# Boost_12V.net
KiCad netlist of a schematic drawn in Altium Designer
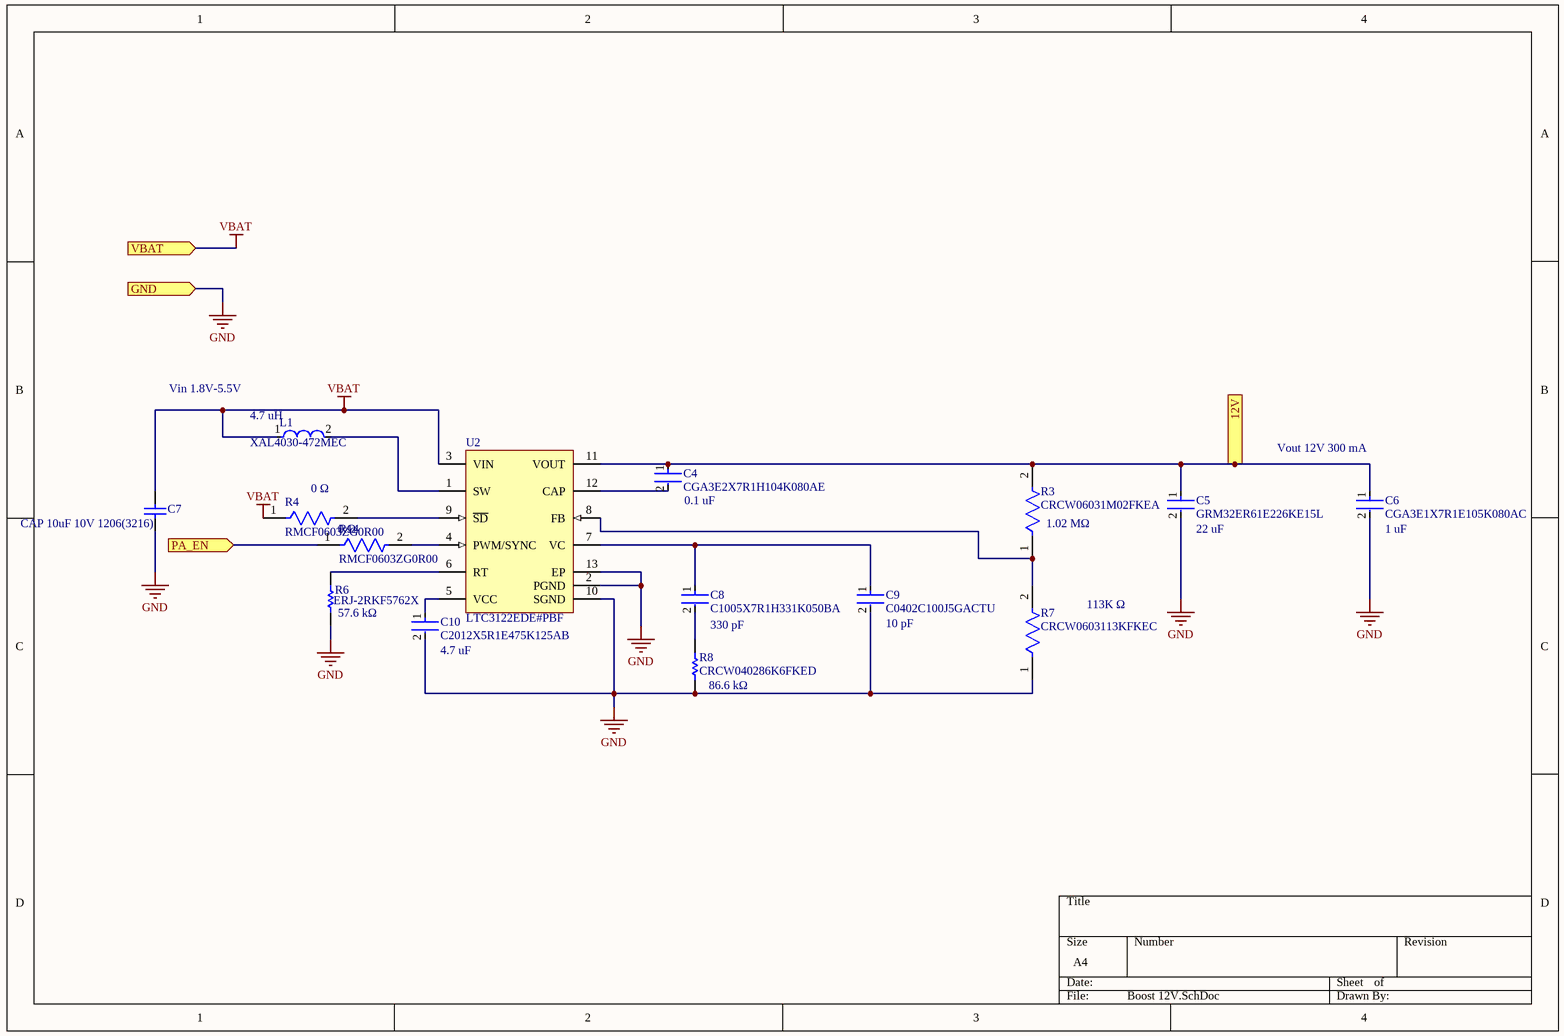
[diagram p0: Boost 12V.SchDoc]

(export (version "E")
  (design (tool "Eeschema 10.0.6"))
  (components
    (comp (ref "C4")
      (value "CGA3E2X7R1H104K080AE")
      (footprint "FP-CGA3E-0_3-0_1-IPC_A")
      (description "Cap Ceramic 100nF 50V X7R 10% Pad SMD 0603 +125°C Automotive T/R")
      (fields (field (name "TOLERANCE") "10%"))
      (libsource (lib "Altium Content Vault") (part "b4654b650e69147ec39a6b967a45e02"))
    )
    (comp (ref "C5")
      (value "GRM32ER61E226KE15L")
      (footprint "FP-GRM32-MFG")
      (description "CAP CER 22UF 25V X5R 1210")
      (fields
        (field (name "TOLERANCE") "10%")
        (field (name "MANUFACTURER") "Murata Electronics North America")
      )
      (libsource (lib "Altium Content Vault") (part "11868f565c42a9108669ba33697ecf6"))
    )
    (comp (ref "C6")
      (value "CGA3E1X7R1E105K080AC")
      (footprint "FP-CGA3E-0_3-0_1-IPC_A")
      (description "Cap Ceramic 1uF 25V X7R 10% Pad SMD 0603 +125°C Automotive T/R")
      (fields (field (name "VOLTAGE") "25V") (field (name "TOLERANCE") "10%"))
      (libsource (lib "Altium Content Vault") (part "b4654b650e69147ec39a6b967a45e02"))
    )
    (comp (ref "C7")
      (value "CAP 10uF 10V 1206(3216)")
      (footprint "CAPC1206(3216)190_L")
      (description "CAP 10uF 10V ±10% 1206 (3216 Metric) Thickness 1.9mm SMD")
      (fields (field (name "TOLERANCE") "Â±10%"))
      (libsource (lib "Altium Content Vault") (part "CAP"))
    )
    (comp (ref "C8")
      (value "C1005X7R1H331K050BA")
      (footprint "FP-C1005-050-0_05-IPC_B")
      (description "Multilayer Ceramic Capacitors 330pF ±10% 50V X7R SMD 0402")
      (fields (field (name "TOLERANCE") "10%"))
      (libsource (lib "Altium Content Vault") (part "b4654b650e69147ec39a6b967a45e02"))
    )
    (comp (ref "C9")
      (value "C0402C100J5GACTU")
      (footprint "FP-C0402-BB-MFG")
      (fields
        (field (name "MANUFACTURER") "Kemet")
        (field (name "OCTOPART") "https://octopart.com/c0402c100j5gactu-kemet-108448")
        (field (name "TOLERANCE") "0.05")
      )
      (libsource (lib "Altium Content Vault") (part "b4654b650e69147ec39a6b967a45e02"))
    )
    (comp (ref "C10")
      (value "C2012X5R1E475K125AB")
      (footprint "FP-C2012-125-0_2-MFG")
      (description "Multilayer Ceramic Capacitors 4.7μF ±10% 25V X5R SMD 0805")
      (fields (field (name "VOLTAGE") "25V") (field (name "TOLERANCE") "10%"))
      (libsource (lib "Altium Content Vault") (part "b4654b650e69147ec39a6b967a45e02"))
    )
    (comp (ref "L1")
      (value "XAL4030-472MEC")
      (footprint "FP-XAL4030-472MEC-MFG")
      (description "Power Inductor (SMD), 4.7 µH, 5.1 A, Shielded, 4.5 A, XAL40xx Series, 4mm x 4mm x 3.1mm")
      (fields (field (name "TOLERANCE") "20%"))
      (libsource (lib "Altium Content Vault") (part "725321dda6339637d4d059423bc1c3c"))
    )
    (comp (ref "R3")
      (value "CRCW06031M02FKEA")
      (footprint "FP-CRCW0603-e3-IPC_A")
      (description "RES Thick Film, 1.02MΩ, 1%, 0.1W, 100ppm/°C, 0603")
      (fields (field (name "TOLERANCE") "1%"))
      (libsource (lib "Altium Content Vault") (part "1029c3af85768c4190bb7ad29bc67b5"))
    )
    (comp (ref "R4")
      (value "RMCF0603ZG0R00")
      (footprint "FP-RMCF0603-IPC_B")
      (description "0Ω ±0 0.1W 0603 Thick Film Chip Resistor AEC-Q200 compliant")
      (libsource (lib "Altium Content Vault") (part "1029c3af85768c4190bb7ad29bc67b5"))
    )
    (comp (ref "R6")
      (value "ERJ-2RKF5762X")
      (footprint "RESC1005X40X25NL05T05")
      (fields (field (name "MANUFACTURER") "Panasonic"))
      (libsource (lib "Altium Content Vault") (part "RES"))
    )
    (comp (ref "R7")
      (value "CRCW0603113KFKEC")
      (footprint "FP-CRCW0603-e3-MFG")
      (description "RES Thick Film, 113kΩ, 1%, 0.1W, 100ppm/°C, 0603")
      (fields (field (name "TOLERANCE") "1%"))
      (libsource (lib "Altium Content Vault") (part "1029c3af85768c4190bb7ad29bc67b5"))
    )
    (comp (ref "R8")
      (value "CRCW040286K6FKED")
      (footprint "RESC1005X40X25NL05T05")
      (fields (field (name "MANUFACTURER") "Vishay Dale"))
      (libsource (lib "Altium Content Vault") (part "RES"))
    )
    (comp (ref "R14")
      (value "RMCF0603ZG0R00")
      (footprint "FP-RMCF0603-IPC_B")
      (description "0Ω ±0 0.1W 0603 Thick Film Chip Resistor AEC-Q200 compliant")
      (libsource (lib "Altium Content Vault") (part "1029c3af85768c4190bb7ad29bc67b5"))
    )
    (comp (ref "U2")
      (value "LTC3122EDE#PBF")
      (footprint "LT-DE-UE-12_V")
      (fields (field (name "MANUFACTURER") "Linear Technology"))
      (libsource (lib "Altium Content Vault") (part "LT-LTC3122-X-12"))
    )
  )
  (nets
    (net (code "1") (name "/12V") (class "Default")
      (node (ref "C4") (pin "1") (pinfunction "1_1") (pintype "passive"))
      (node (ref "C5") (pin "1") (pinfunction "1_1") (pintype "passive"))
      (node (ref "C6") (pin "1") (pinfunction "1_1") (pintype "passive"))
      (node (ref "R3") (pin "2") (pinfunction "2_2") (pintype "passive"))
      (node (ref "U2") (pin "11") (pinfunction "VOUT_11") (pintype "power_in"))
    )
    (net (code "2") (name "/PA_EN") (class "Default")
      (node (ref "R14") (pin "1") (pinfunction "1_1") (pintype "passive"))
    )
    (net (code "3") (name "GND") (class "Default")
      (node (ref "C10") (pin "2") (pinfunction "2_2") (pintype "passive"))
      (node (ref "C5") (pin "2") (pinfunction "2_2") (pintype "passive"))
      (node (ref "C6") (pin "2") (pinfunction "2_2") (pintype "passive"))
      (node (ref "C7") (pin "1") (pinfunction "1_1") (pintype "passive"))
      (node (ref "C9") (pin "2") (pinfunction "2_2") (pintype "passive"))
      (node (ref "R6") (pin "1") (pinfunction "1_1") (pintype "passive"))
      (node (ref "R7") (pin "1") (pinfunction "1_1") (pintype "passive"))
      (node (ref "R8") (pin "1") (pinfunction "1_1") (pintype "passive"))
      (node (ref "U2") (pin "10") (pinfunction "SGND_10") (pintype "power_in"))
      (node (ref "U2") (pin "13") (pinfunction "EP_13") (pintype "power_in"))
      (node (ref "U2") (pin "2") (pinfunction "PGND_2") (pintype "power_in"))
    )
    (net (code "4") (name "Net-(C8-Pad2)") (class "Default")
      (node (ref "C8") (pin "2") (pinfunction "2_2") (pintype "passive"))
      (node (ref "R8") (pin "2") (pinfunction "2_2") (pintype "passive"))
    )
    (net (code "5") (name "Net-(U2-CAP)") (class "Default")
      (node (ref "C4") (pin "2") (pinfunction "2_2") (pintype "passive"))
      (node (ref "U2") (pin "12") (pinfunction "CAP_12") (pintype "passive"))
    )
    (net (code "6") (name "Net-(U2-FB)") (class "Default")
      (node (ref "R3") (pin "1") (pinfunction "1_1") (pintype "passive"))
      (node (ref "R7") (pin "2") (pinfunction "2_2") (pintype "passive"))
      (node (ref "U2") (pin "8") (pinfunction "FB_8") (pintype "input"))
    )
    (net (code "7") (name "Net-(U2-PWM{slash}SYNC)") (class "Default")
      (node (ref "R14") (pin "2") (pinfunction "2_2") (pintype "passive"))
      (node (ref "U2") (pin "4") (pinfunction "PWM/SYNC_4") (pintype "input"))
    )
    (net (code "8") (name "Net-(U2-RT)") (class "Default")
      (node (ref "R6") (pin "2") (pinfunction "2_2") (pintype "passive"))
      (node (ref "U2") (pin "6") (pinfunction "RT_6") (pintype "passive"))
    )
    (net (code "9") (name "Net-(U2-SW)") (class "Default")
      (node (ref "L1") (pin "2") (pinfunction "2_2") (pintype "passive"))
      (node (ref "U2") (pin "1") (pinfunction "SW_1") (pintype "passive"))
    )
    (net (code "10") (name "Net-(U2-VC)") (class "Default")
      (node (ref "C8") (pin "1") (pinfunction "1_1") (pintype "passive"))
      (node (ref "C9") (pin "1") (pinfunction "1_1") (pintype "passive"))
      (node (ref "U2") (pin "7") (pinfunction "VC_7") (pintype "passive"))
    )
    (net (code "11") (name "Net-(U2-VCC)") (class "Default")
      (node (ref "C10") (pin "1") (pinfunction "1_1") (pintype "passive"))
      (node (ref "U2") (pin "5") (pinfunction "VCC_5") (pintype "power_in"))
    )
    (net (code "12") (name "Net-(U2-~{SD})") (class "Default")
      (node (ref "R4") (pin "2") (pinfunction "2_2") (pintype "passive"))
      (node (ref "U2") (pin "9") (pinfunction "~{SD}_9") (pintype "input"))
    )
    (net (code "13") (name "VBAT") (class "Default")
      (node (ref "C7") (pin "2") (pinfunction "2_2") (pintype "passive"))
      (node (ref "L1") (pin "1") (pinfunction "1_1") (pintype "passive"))
      (node (ref "R4") (pin "1") (pinfunction "1_1") (pintype "passive"))
      (node (ref "U2") (pin "3") (pinfunction "VIN_3") (pintype "power_in"))
    )
  )
)
